# SCH_Joker_2025-09-11.net
KiCad netlist of a schematic drawn in EasyEDA
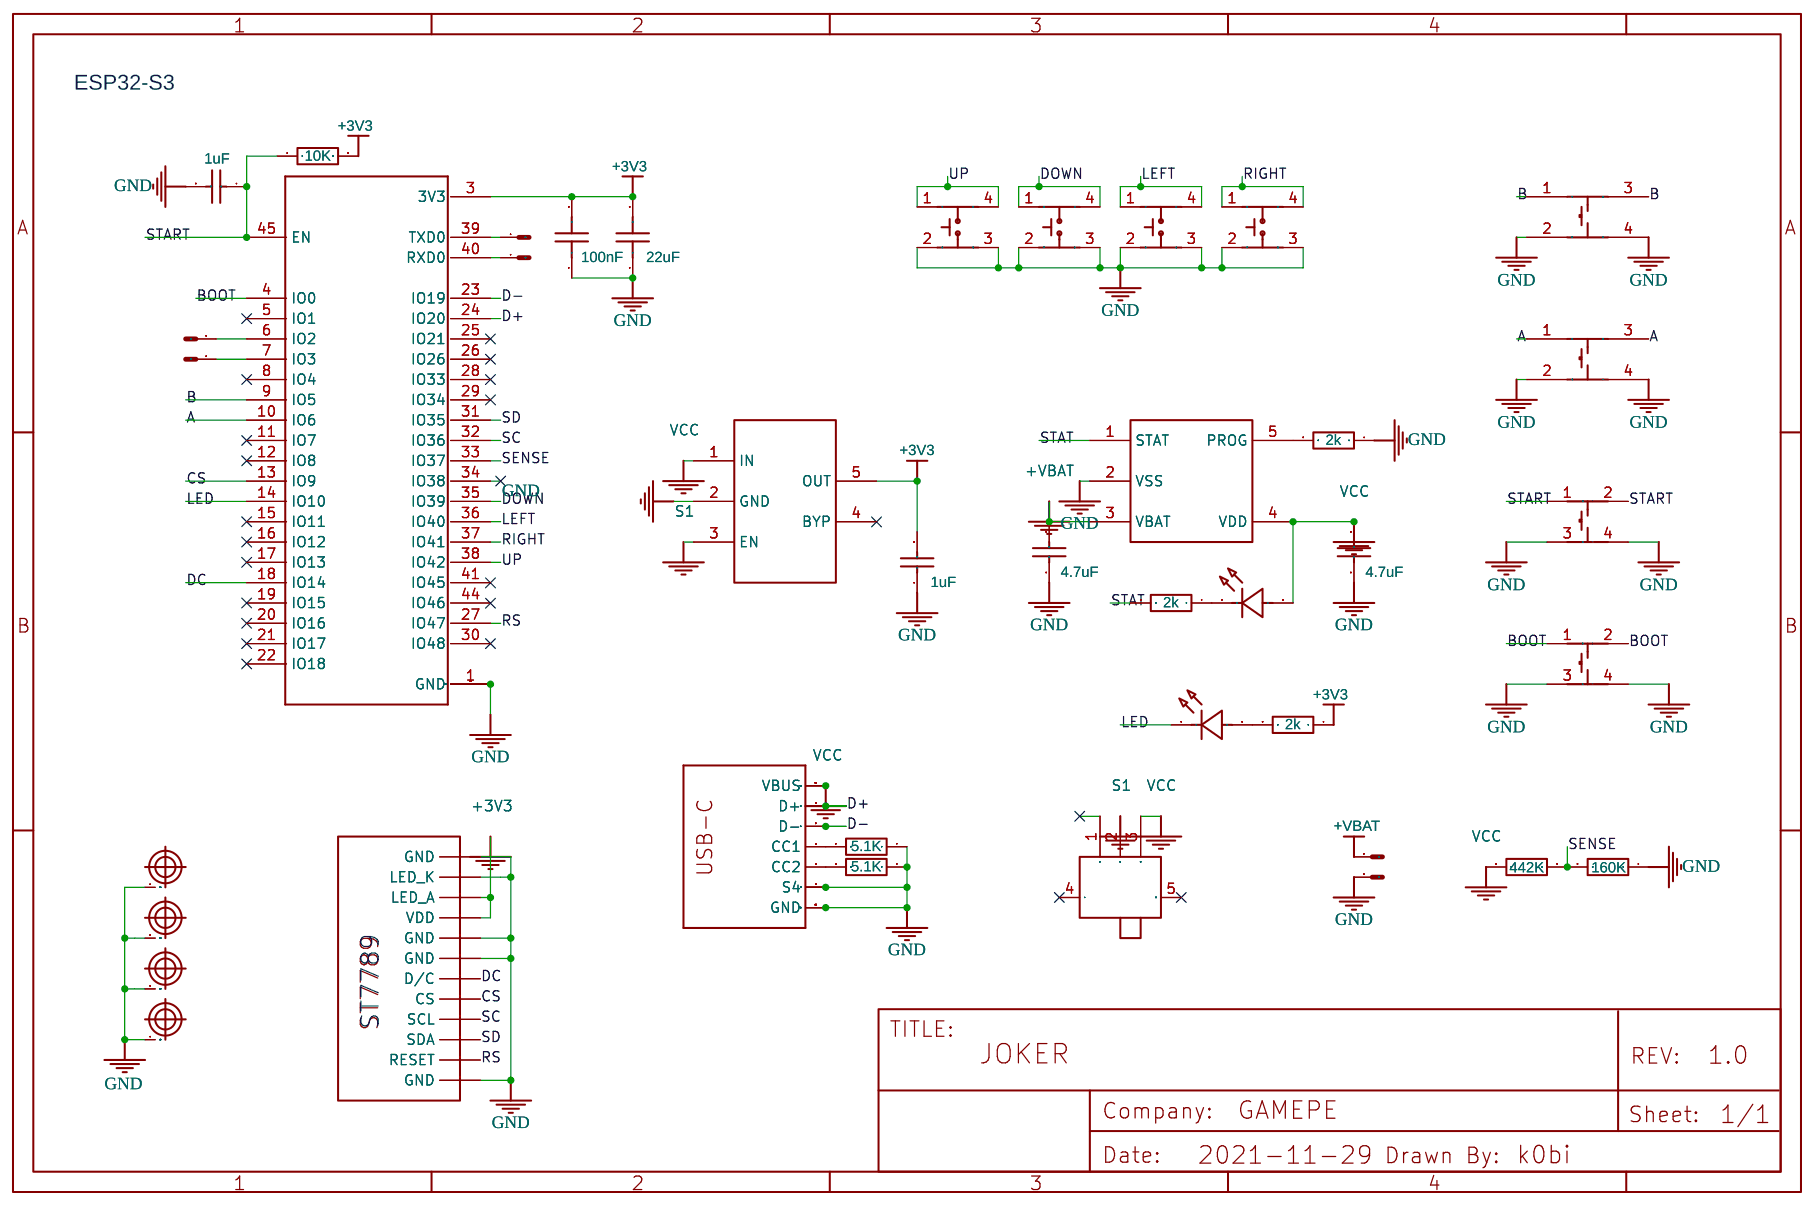
[diagram p0: schematic sheet]

(export (version "E")
  (design (tool "Eeschema 10.0.6"))
  (components
    (comp (ref "C2")
      (value "1uF")
      (fields
        (field (name "Manufacturer Part") "CL10A105KA8NNNC")
        (field (name "Manufacturer") "SAMSUNG(三星)")
      )
      (libsource (lib "") (part "CL10A105KA8NNNC"))
    )
    (comp (ref "C3")
      (value "100nF")
      (fields
        (field (name "Manufacturer Part") "CL10B104KA8NNNC")
        (field (name "Manufacturer") "SAMSUNG(三星)")
      )
      (libsource (lib "") (part "CL10B104KA8NNNC"))
    )
    (comp (ref "C4")
      (value "22uF")
      (fields
        (field (name "Manufacturer Part") "CL10A226MP8NUNE")
        (field (name "Manufacturer") "SAMSUNG(三星)")
      )
      (libsource (lib "") (part "CL10A226MP8NUNE"))
    )
    (comp (ref "C5")
      (value "1uF")
      (fields (field (name "Manufacturer Part") "CC0603MRX5R6BB106") (field (name "Manufacturer") "YAGEO"))
      (libsource (lib "") (part "CC0603MRX5R6BB106"))
    )
    (comp (ref "C6")
      (value "4.7uF")
      (fields (field (name "Manufacturer Part") "CL10A105KA8NNNC") (field (name "Manufacturer") "SAMSUNG"))
      (libsource (lib "") (part "CL10A105KA8NNNC_1"))
    )
    (comp (ref "C7")
      (value "4.7uF")
      (fields (field (name "Manufacturer Part") "CL10A105KA8NNNC") (field (name "Manufacturer") "SAMSUNG"))
      (libsource (lib "") (part "CL10A105KA8NNNC_1"))
    )
    (comp (ref "H1") (value "M2-MOUNT-HOLE") (libsource (lib "") (part "M2-MOUNT-HOLE")))
    (comp (ref "H2") (value "M2-MOUNT-HOLE") (libsource (lib "") (part "M2-MOUNT-HOLE")))
    (comp (ref "H3") (value "M2-MOUNT-HOLE") (libsource (lib "") (part "M2-MOUNT-HOLE")))
    (comp (ref "H4") (value "M2-MOUNT-HOLE") (libsource (lib "") (part "M2-MOUNT-HOLE")))
    (comp (ref "LED1")
      (value "le")
      (fields
        (field (name "Manufacturer Part") "TZ-P2-0603YGTCS1-0.6T")
        (field (name "Manufacturer") "TUOZHAN")
      )
      (libsource (lib "") (part "TZ-P2-0603YGTCS1-0.6T"))
    )
    (comp (ref "LED2")
      (value "le")
      (fields
        (field (name "Manufacturer Part") "TZ-P2-0603YGTCS1-0.6T")
        (field (name "Manufacturer") "TUOZHAN")
      )
      (libsource (lib "") (part "TZ-P2-0603YGTCS1-0.6T"))
    )
    (comp (ref "R1")
      (value "2k")
      (fields (field (name "Manufacturer Part") "RC0603FR-0710KL") (field (name "Manufacturer") "YAGEO"))
      (libsource (lib "") (part "RC0603FR-0710KL"))
    )
    (comp (ref "R2")
      (value "2k")
      (fields (field (name "Manufacturer Part") "RC0603FR-0710KL") (field (name "Manufacturer") "YAGEO"))
      (libsource (lib "") (part "RC0603FR-0710KL"))
    )
    (comp (ref "R6")
      (value "10K")
      (fields (field (name "Manufacturer Part") "RC0603FR-0710KL") (field (name "Manufacturer") "YAGEO(国巨)"))
      (libsource (lib "") (part "RC0603FR-0710KL_1"))
    )
    (comp (ref "R10")
      (value "5.1K")
      (fields (field (name "Manufacturer Part") "RC0603FR-0710KL") (field (name "Manufacturer") "YAGEO"))
      (libsource (lib "") (part "RC0603FR-0710KL"))
    )
    (comp (ref "R11")
      (value "5.1K")
      (fields (field (name "Manufacturer Part") "RC0603FR-0710KL") (field (name "Manufacturer") "YAGEO"))
      (libsource (lib "") (part "RC0603FR-0710KL"))
    )
    (comp (ref "R13")
      (value "2k")
      (fields (field (name "Manufacturer Part") "RC0603FR-0710KL") (field (name "Manufacturer") "YAGEO"))
      (libsource (lib "") (part "RC0603FR-0710KL"))
    )
    (comp (ref "R15")
      (value "442K")
      (fields (field (name "Manufacturer Part") "RC0603FR-0710KL") (field (name "Manufacturer") "YAGEO"))
      (libsource (lib "") (part "RC0603FR-0710KL"))
    )
    (comp (ref "R16")
      (value "160K")
      (fields (field (name "Manufacturer Part") "RC0603FR-0710KL") (field (name "Manufacturer") "YAGEO"))
      (libsource (lib "") (part "RC0603FR-0710KL"))
    )
    (comp (ref "SW1")
      (value "SKRRAAE010")
      (fields (field (name "Manufacturer") "ALPSALPINE(阿尔卑斯阿尔派)"))
      (libsource (lib "") (part "SKRRAAE010"))
    )
    (comp (ref "SW2")
      (value "SKRRAAE010")
      (fields (field (name "Manufacturer") "ALPSALPINE(阿尔卑斯阿尔派)"))
      (libsource (lib "") (part "SKRRAAE010"))
    )
    (comp (ref "SW3")
      (value "TS-2630-B")
      (fields (field (name "Manufacturer") "XKB Connectivity(中国星坤)"))
      (libsource (lib "") (part "TS-2630-B"))
    )
    (comp (ref "SW4")
      (value "TS-2630-B")
      (fields (field (name "Manufacturer") "XKB Connectivity(中国星坤)"))
      (libsource (lib "") (part "TS-2630-B"))
    )
    (comp (ref "SW6")
      (value "C219784")
      (fields
        (field (name "Manufacturer Part") "SKTKABE010")
        (field (name "Manufacturer") "ALPSALPINE(阿尔卑斯阿尔派)")
      )
      (libsource (lib "") (part "C219784"))
    )
    (comp (ref "SW7")
      (value "C219784")
      (fields
        (field (name "Manufacturer Part") "SKTKABE010")
        (field (name "Manufacturer") "ALPSALPINE(阿尔卑斯阿尔派)")
      )
      (libsource (lib "") (part "C219784"))
    )
    (comp (ref "SW8")
      (value "C219784")
      (fields
        (field (name "Manufacturer Part") "SKTKABE010")
        (field (name "Manufacturer") "ALPSALPINE(阿尔卑斯阿尔派)")
      )
      (libsource (lib "") (part "C219784"))
    )
    (comp (ref "SW9")
      (value "C219784")
      (fields
        (field (name "Manufacturer Part") "SKTKABE010")
        (field (name "Manufacturer") "ALPSALPINE(阿尔卑斯阿尔派)")
      )
      (libsource (lib "") (part "C219784"))
    )
    (comp (ref "SW10")
      (value "MINI MSK12CO2")
      (fields (field (name "Manufacturer") "SHOU HAN(首韩)"))
      (libsource (lib "") (part "MINI MSK12CO2"))
    )
    (comp (ref "TP4") (value "TP/SP-1.5X1.0") (libsource (lib "") (part "TP/SP-1.5X1.0")))
    (comp (ref "TP6") (value "TP/SP-1.5X1.0") (libsource (lib "") (part "TP/SP-1.5X1.0")))
    (comp (ref "TP13") (value "TP/SP-1.5X1.0") (libsource (lib "") (part "TP/SP-1.5X1.0_1")))
    (comp (ref "TP14") (value "TP/SP-1.5X1.0") (libsource (lib "") (part "TP/SP-1.5X1.0_1")))
    (comp (ref "TP15") (value "TP/SP-1.5X1.0") (libsource (lib "") (part "TP/SP-1.5X1.0")))
    (comp (ref "TP16") (value "TP/SP-1.5X1.0") (libsource (lib "") (part "TP/SP-1.5X1.0")))
    (comp (ref "U1") (value "ESP32-S3-MINI-1-N8") (libsource (lib "") (part "ESP32-S3-MINI-1-N8")))
    (comp (ref "U2")
      (value "SPX3819M5-L-3-3/TR")
      (fields (field (name "Manufacturer") "EXAR"))
      (libsource (lib "") (part "SPX3819M5-L-3-3/TR"))
    )
    (comp (ref "U3")
      (value "MCP73831T-2ATI/OT")
      (fields (field (name "Manufacturer") "MICROCHIP"))
      (libsource (lib "") (part "MCP73831T-2ATI/OT"))
    )
    (comp (ref "U4")
      (value "1.3\" RGB TFT LCD")
      (fields
        (field (name "Manufacturer Part") "N133-2424TCBIG01-H12")
        (field (name "Manufacturer") "Shenzhen Allvision Tech")
      )
      (libsource (lib "") (part "1.3{dblquote} RGB TFT LCD"))
    )
    (comp (ref "U6") (value "C136423") (libsource (lib "") (part "C136423")))
  )
  (nets
    (net (code "1") (name "+3V3") (class "Default")
      (node (ref "C3") (pin "2") (pinfunction "2_2") (pintype "unspecified"))
      (node (ref "C4") (pin "2") (pinfunction "2_2") (pintype "unspecified"))
      (node (ref "C5") (pin "2") (pinfunction "2_2") (pintype "input"))
      (node (ref "R2") (pin "1") (pinfunction "1_1") (pintype "input"))
      (node (ref "R6") (pin "2") (pinfunction "2_2") (pintype "input"))
      (node (ref "U1") (pin "3") (pinfunction "3V3_3") (pintype "unspecified"))
      (node (ref "U2") (pin "5") (pinfunction "OUT_5") (pintype "unspecified"))
      (node (ref "U4") (pin "3") (pinfunction "LED_A_3") (pintype "unspecified"))
      (node (ref "U4") (pin "4") (pinfunction "VDD_4") (pintype "unspecified"))
    )
    (net (code "2") (name "+VBAT") (class "Default")
      (node (ref "C6") (pin "1") (pinfunction "1_1") (pintype "input"))
      (node (ref "TP16") (pin "1") (pinfunction "S_1") (pintype "bidirectional"))
      (node (ref "U3") (pin "3") (pinfunction "VBAT_3") (pintype "unspecified"))
    )
    (net (code "3") (name "/A") (class "Default")
      (node (ref "SW1") (pin "1") (pinfunction "1_1") (pintype "unspecified"))
      (node (ref "SW1") (pin "3") (pinfunction "3_3") (pintype "unspecified"))
      (node (ref "U1") (pin "10") (pinfunction "IO6_10") (pintype "unspecified"))
    )
    (net (code "4") (name "/B") (class "Default")
      (node (ref "SW2") (pin "1") (pinfunction "1_1") (pintype "unspecified"))
      (node (ref "SW2") (pin "3") (pinfunction "3_3") (pintype "unspecified"))
      (node (ref "U1") (pin "9") (pinfunction "IO5_9") (pintype "unspecified"))
    )
    (net (code "5") (name "/BOOT") (class "Default")
      (node (ref "SW4") (pin "1") (pinfunction "1_1") (pintype "unspecified"))
      (node (ref "SW4") (pin "2") (pinfunction "2_2") (pintype "unspecified"))
      (node (ref "U1") (pin "4") (pinfunction "IO0_4") (pintype "unspecified"))
    )
    (net (code "6") (name "/CS") (class "Default")
      (node (ref "U1") (pin "13") (pinfunction "IO9_13") (pintype "unspecified"))
      (node (ref "U4") (pin "8") (pinfunction "CS_8") (pintype "unspecified"))
    )
    (net (code "7") (name "/D+") (class "Default")
      (node (ref "U1") (pin "24") (pinfunction "IO20_24") (pintype "unspecified"))
      (node (ref "U6") (pin "A6") (pinfunction "D+_A6") (pintype "bidirectional"))
      (node (ref "U6") (pin "B6") (pinfunction "D+_B6") (pintype "bidirectional"))
    )
    (net (code "8") (name "/D-") (class "Default")
      (node (ref "U1") (pin "23") (pinfunction "IO19_23") (pintype "unspecified"))
      (node (ref "U6") (pin "A7") (pinfunction "D-_A7") (pintype "bidirectional"))
      (node (ref "U6") (pin "B7") (pinfunction "D-_B7") (pintype "bidirectional"))
    )
    (net (code "9") (name "/DC") (class "Default")
      (node (ref "U1") (pin "18") (pinfunction "IO14_18") (pintype "unspecified"))
      (node (ref "U4") (pin "7") (pinfunction "D/C_7") (pintype "unspecified"))
    )
    (net (code "10") (name "/DOWN") (class "Default")
      (node (ref "SW8") (pin "1") (pinfunction "1_1") (pintype "unspecified"))
      (node (ref "SW8") (pin "4") (pinfunction "4_4") (pintype "unspecified"))
      (node (ref "U1") (pin "35") (pinfunction "IO39_35") (pintype "unspecified"))
    )
    (net (code "11") (name "/LED") (class "Default")
      (node (ref "LED2") (pin "1") (pinfunction "K_1") (pintype "unspecified"))
      (node (ref "U1") (pin "14") (pinfunction "IO10_14") (pintype "unspecified"))
    )
    (net (code "12") (name "/LEFT") (class "Default")
      (node (ref "SW7") (pin "1") (pinfunction "1_1") (pintype "unspecified"))
      (node (ref "SW7") (pin "4") (pinfunction "4_4") (pintype "unspecified"))
      (node (ref "U1") (pin "36") (pinfunction "IO40_36") (pintype "unspecified"))
    )
    (net (code "13") (name "/RIGHT") (class "Default")
      (node (ref "SW6") (pin "1") (pinfunction "1_1") (pintype "unspecified"))
      (node (ref "SW6") (pin "4") (pinfunction "4_4") (pintype "unspecified"))
      (node (ref "U1") (pin "37") (pinfunction "IO41_37") (pintype "unspecified"))
    )
    (net (code "14") (name "/RS") (class "Default")
      (node (ref "U1") (pin "27") (pinfunction "IO47_27") (pintype "unspecified"))
      (node (ref "U4") (pin "11") (pinfunction "RESET_11") (pintype "unspecified"))
    )
    (net (code "15") (name "/SC") (class "Default")
      (node (ref "U1") (pin "32") (pinfunction "IO36_32") (pintype "unspecified"))
      (node (ref "U4") (pin "9") (pinfunction "SCL_9") (pintype "unspecified"))
    )
    (net (code "16") (name "/SD") (class "Default")
      (node (ref "U1") (pin "31") (pinfunction "IO35_31") (pintype "unspecified"))
      (node (ref "U4") (pin "10") (pinfunction "SDA_10") (pintype "unspecified"))
    )
    (net (code "17") (name "/SENSE") (class "Default")
      (node (ref "R15") (pin "1") (pinfunction "1_1") (pintype "input"))
      (node (ref "R16") (pin "2") (pinfunction "2_2") (pintype "input"))
      (node (ref "U1") (pin "33") (pinfunction "IO37_33") (pintype "unspecified"))
    )
    (net (code "18") (name "/START") (class "Default")
      (node (ref "C2") (pin "1") (pinfunction "1_1") (pintype "input"))
      (node (ref "R6") (pin "1") (pinfunction "1_1") (pintype "input"))
      (node (ref "SW3") (pin "1") (pinfunction "1_1") (pintype "unspecified"))
      (node (ref "SW3") (pin "2") (pinfunction "2_2") (pintype "unspecified"))
      (node (ref "U1") (pin "45") (pinfunction "EN_45") (pintype "unspecified"))
    )
    (net (code "19") (name "/STAT") (class "Default")
      (node (ref "R1") (pin "2") (pinfunction "2_2") (pintype "input"))
      (node (ref "U3") (pin "1") (pinfunction "STAT_1") (pintype "unspecified"))
    )
    (net (code "20") (name "/UP") (class "Default")
      (node (ref "SW9") (pin "1") (pinfunction "1_1") (pintype "unspecified"))
      (node (ref "SW9") (pin "4") (pinfunction "4_4") (pintype "unspecified"))
      (node (ref "U1") (pin "38") (pinfunction "IO42_38") (pintype "unspecified"))
    )
    (net (code "21") (name "GND") (class "Default")
      (node (ref "C2") (pin "2") (pinfunction "2_2") (pintype "input"))
      (node (ref "C3") (pin "1") (pinfunction "1_1") (pintype "unspecified"))
      (node (ref "C4") (pin "1") (pinfunction "1_1") (pintype "unspecified"))
      (node (ref "C5") (pin "1") (pinfunction "1_1") (pintype "input"))
      (node (ref "C6") (pin "2") (pinfunction "2_2") (pintype "input"))
      (node (ref "C7") (pin "2") (pinfunction "2_2") (pintype "input"))
      (node (ref "H1") (pin "1") (pinfunction "GND_1") (pintype "passive"))
      (node (ref "H2") (pin "1") (pinfunction "GND_1") (pintype "passive"))
      (node (ref "H3") (pin "1") (pinfunction "GND_1") (pintype "passive"))
      (node (ref "H4") (pin "1") (pinfunction "GND_1") (pintype "passive"))
      (node (ref "R10") (pin "1") (pinfunction "1_1") (pintype "input"))
      (node (ref "R11") (pin "1") (pinfunction "1_1") (pintype "input"))
      (node (ref "R13") (pin "1") (pinfunction "1_1") (pintype "input"))
      (node (ref "R16") (pin "1") (pinfunction "1_1") (pintype "input"))
      (node (ref "SW1") (pin "2") (pinfunction "2_2") (pintype "unspecified"))
      (node (ref "SW1") (pin "4") (pinfunction "4_4") (pintype "unspecified"))
      (node (ref "SW2") (pin "2") (pinfunction "2_2") (pintype "unspecified"))
      (node (ref "SW2") (pin "4") (pinfunction "4_4") (pintype "unspecified"))
      (node (ref "SW3") (pin "3") (pinfunction "3_3") (pintype "unspecified"))
      (node (ref "SW3") (pin "4") (pinfunction "4_4") (pintype "unspecified"))
      (node (ref "SW4") (pin "3") (pinfunction "3_3") (pintype "unspecified"))
      (node (ref "SW4") (pin "4") (pinfunction "4_4") (pintype "unspecified"))
      (node (ref "SW6") (pin "2") (pinfunction "2_2") (pintype "unspecified"))
      (node (ref "SW6") (pin "3") (pinfunction "3_3") (pintype "unspecified"))
      (node (ref "SW7") (pin "2") (pinfunction "2_2") (pintype "unspecified"))
      (node (ref "SW7") (pin "3") (pinfunction "3_3") (pintype "unspecified"))
      (node (ref "SW8") (pin "2") (pinfunction "2_2") (pintype "unspecified"))
      (node (ref "SW8") (pin "3") (pinfunction "3_3") (pintype "unspecified"))
      (node (ref "SW9") (pin "2") (pinfunction "2_2") (pintype "unspecified"))
      (node (ref "SW9") (pin "3") (pinfunction "3_3") (pintype "unspecified"))
      (node (ref "TP15") (pin "1") (pinfunction "S_1") (pintype "bidirectional"))
      (node (ref "U1") (pin "1") (pinfunction "GND_1") (pintype "unspecified"))
      (node (ref "U1") (pin "2") (pinfunction "GND_2") (pintype "unspecified"))
      (node (ref "U1") (pin "42") (pinfunction "GND_42") (pintype "unspecified"))
      (node (ref "U1") (pin "43") (pinfunction "GND_43") (pintype "unspecified"))
      (node (ref "U1") (pin "46") (pinfunction "GND_46") (pintype "unspecified"))
      (node (ref "U1") (pin "47") (pinfunction "GND_47") (pintype "unspecified"))
      (node (ref "U1") (pin "48") (pinfunction "GND_48") (pintype "unspecified"))
      (node (ref "U1") (pin "49") (pinfunction "GND_49") (pintype "unspecified"))
      (node (ref "U1") (pin "50") (pinfunction "GND_50") (pintype "unspecified"))
      (node (ref "U1") (pin "51") (pinfunction "GND_51") (pintype "unspecified"))
      (node (ref "U1") (pin "52") (pinfunction "GND_52") (pintype "unspecified"))
      (node (ref "U1") (pin "53") (pinfunction "GND_53") (pintype "unspecified"))
      (node (ref "U1") (pin "54") (pinfunction "GND_54") (pintype "unspecified"))
      (node (ref "U1") (pin "55") (pinfunction "GND_55") (pintype "unspecified"))
      (node (ref "U1") (pin "56") (pinfunction "GND_56") (pintype "unspecified"))
      (node (ref "U1") (pin "57") (pinfunction "GND_57") (pintype "unspecified"))
      (node (ref "U1") (pin "58") (pinfunction "GND_58") (pintype "unspecified"))
      (node (ref "U1") (pin "59") (pinfunction "GND_59") (pintype "unspecified"))
      (node (ref "U1") (pin "60") (pinfunction "GND_60") (pintype "unspecified"))
      (node (ref "U1") (pin "61") (pinfunction "GND_61") (pintype "unspecified"))
      (node (ref "U1") (pin "61_1") (pinfunction "GND_61_1") (pintype "unspecified"))
      (node (ref "U1") (pin "61_2") (pinfunction "GND_61_2") (pintype "unspecified"))
      (node (ref "U1") (pin "61_3") (pinfunction "GND_61_3") (pintype "unspecified"))
      (node (ref "U1") (pin "61_4") (pinfunction "GND_61_4") (pintype "unspecified"))
      (node (ref "U1") (pin "61_5") (pinfunction "GND_61_5") (pintype "unspecified"))
      (node (ref "U1") (pin "61_6") (pinfunction "GND_61_6") (pintype "unspecified"))
      (node (ref "U1") (pin "61_7") (pinfunction "GND_61_7") (pintype "unspecified"))
      (node (ref "U1") (pin "61_8") (pinfunction "GND_61_8") (pintype "unspecified"))
      (node (ref "U1") (pin "62") (pinfunction "GND_62") (pintype "unspecified"))
      (node (ref "U1") (pin "63") (pinfunction "GND_63") (pintype "unspecified"))
      (node (ref "U1") (pin "64") (pinfunction "GND_64") (pintype "unspecified"))
      (node (ref "U1") (pin "65") (pinfunction "GND_65") (pintype "unspecified"))
      (node (ref "U2") (pin "2") (pinfunction "GND_2") (pintype "unspecified"))
      (node (ref "U3") (pin "2") (pinfunction "VSS_2") (pintype "unspecified"))
      (node (ref "U4") (pin "1") (pinfunction "GND_1") (pintype "unspecified"))
      (node (ref "U4") (pin "12") (pinfunction "GND_12") (pintype "unspecified"))
      (node (ref "U4") (pin "2") (pinfunction "LED_K_2") (pintype "unspecified"))
      (node (ref "U4") (pin "5") (pinfunction "GND_5") (pintype "unspecified"))
      (node (ref "U4") (pin "6") (pinfunction "GND_6") (pintype "unspecified"))
      (node (ref "U6") (pin "1") (pinfunction "S4_1") (pintype "bidirectional"))
      (node (ref "U6") (pin "2") (pinfunction "S4_2") (pintype "bidirectional"))
      (node (ref "U6") (pin "3") (pinfunction "S4_3") (pintype "bidirectional"))
      (node (ref "U6") (pin "4") (pinfunction "S4_4") (pintype "bidirectional"))
      (node (ref "U6") (pin "A1-B12") (pinfunction "GND_A1-B12") (pintype "bidirectional"))
      (node (ref "U6") (pin "B1-A12") (pinfunction "GND_B1-A12") (pintype "bidirectional"))
    )
    (net (code "22") (name "Net-(LED1-K)") (class "Default")
      (node (ref "LED1") (pin "1") (pinfunction "K_1") (pintype "unspecified"))
      (node (ref "R1") (pin "1") (pinfunction "1_1") (pintype "input"))
    )
    (net (code "23") (name "Net-(LED2-A)") (class "Default")
      (node (ref "LED2") (pin "2") (pinfunction "A_2") (pintype "unspecified"))
      (node (ref "R2") (pin "2") (pinfunction "2_2") (pintype "input"))
    )
    (net (code "24") (name "Net-(TP4-S)") (class "Default")
      (node (ref "TP4") (pin "1") (pinfunction "S_1") (pintype "bidirectional"))
      (node (ref "U1") (pin "39") (pinfunction "TXD0_39") (pintype "unspecified"))
    )
    (net (code "25") (name "Net-(TP6-S)") (class "Default")
      (node (ref "TP6") (pin "1") (pinfunction "S_1") (pintype "bidirectional"))
      (node (ref "U1") (pin "40") (pinfunction "RXD0_40") (pintype "unspecified"))
    )
    (net (code "26") (name "Net-(TP13-S)") (class "Default")
      (node (ref "TP13") (pin "1") (pinfunction "S_1") (pintype "bidirectional"))
      (node (ref "U1") (pin "7") (pinfunction "IO3_7") (pintype "unspecified"))
    )
    (net (code "27") (name "Net-(TP14-S)") (class "Default")
      (node (ref "TP14") (pin "1") (pinfunction "S_1") (pintype "bidirectional"))
      (node (ref "U1") (pin "6") (pinfunction "IO2_6") (pintype "unspecified"))
    )
    (net (code "28") (name "Net-(U3-PROG)") (class "Default")
      (node (ref "R13") (pin "2") (pinfunction "2_2") (pintype "input"))
      (node (ref "U3") (pin "5") (pinfunction "PROG_5") (pintype "unspecified"))
    )
    (net (code "29") (name "Net-(U6-CC1)") (class "Default")
      (node (ref "R10") (pin "2") (pinfunction "2_2") (pintype "input"))
      (node (ref "U6") (pin "A5") (pinfunction "CC1_A5") (pintype "bidirectional"))
    )
    (net (code "30") (name "Net-(U6-CC2)") (class "Default")
      (node (ref "R11") (pin "2") (pinfunction "2_2") (pintype "input"))
      (node (ref "U6") (pin "B5") (pinfunction "CC2_B5") (pintype "bidirectional"))
    )
    (net (code "31") (name "S1") (class "Default")
      (node (ref "SW10") (pin "2") (pinfunction "2_2") (pintype "unspecified"))
      (node (ref "U2") (pin "3") (pinfunction "EN_3") (pintype "unspecified"))
    )
    (net (code "32") (name "VCC") (class "Default")
      (node (ref "C7") (pin "1") (pinfunction "1_1") (pintype "input"))
      (node (ref "LED1") (pin "2") (pinfunction "A_2") (pintype "unspecified"))
      (node (ref "R15") (pin "2") (pinfunction "2_2") (pintype "input"))
      (node (ref "SW10") (pin "3") (pinfunction "3_3") (pintype "unspecified"))
      (node (ref "U2") (pin "1") (pinfunction "IN_1") (pintype "unspecified"))
      (node (ref "U3") (pin "4") (pinfunction "VDD_4") (pintype "unspecified"))
      (node (ref "U6") (pin "A4-B9") (pinfunction "VBUS_A4-B9") (pintype "bidirectional"))
      (node (ref "U6") (pin "B4-A9") (pinfunction "VBUS_B4-A9") (pintype "bidirectional"))
    )
    (net (code "33") (name "unconnected-(SW10-Pad1)") (class "Default")
      (node (ref "SW10") (pin "1") (pinfunction "1_1") (pintype "unspecified+no_connect"))
    )
    (net (code "34") (name "unconnected-(SW10-Pad4)") (class "Default")
      (node (ref "SW10") (pin "4") (pinfunction "4_4") (pintype "unspecified+no_connect"))
    )
    (net (code "35") (name "unconnected-(SW10-Pad5)") (class "Default")
      (node (ref "SW10") (pin "5") (pinfunction "5_5") (pintype "unspecified+no_connect"))
    )
    (net (code "36") (name "unconnected-(U1-IO1-Pad5)") (class "Default")
      (node (ref "U1") (pin "5") (pinfunction "IO1_5") (pintype "unspecified+no_connect"))
    )
    (net (code "37") (name "unconnected-(U1-IO4-Pad8)") (class "Default")
      (node (ref "U1") (pin "8") (pinfunction "IO4_8") (pintype "unspecified+no_connect"))
    )
    (net (code "38") (name "unconnected-(U1-IO7-Pad11)") (class "Default")
      (node (ref "U1") (pin "11") (pinfunction "IO7_11") (pintype "unspecified+no_connect"))
    )
    (net (code "39") (name "unconnected-(U1-IO8-Pad12)") (class "Default")
      (node (ref "U1") (pin "12") (pinfunction "IO8_12") (pintype "unspecified+no_connect"))
    )
    (net (code "40") (name "unconnected-(U1-IO11-Pad15)") (class "Default")
      (node (ref "U1") (pin "15") (pinfunction "IO11_15") (pintype "unspecified+no_connect"))
    )
    (net (code "41") (name "unconnected-(U1-IO12-Pad16)") (class "Default")
      (node (ref "U1") (pin "16") (pinfunction "IO12_16") (pintype "unspecified+no_connect"))
    )
    (net (code "42") (name "unconnected-(U1-IO13-Pad17)") (class "Default")
      (node (ref "U1") (pin "17") (pinfunction "IO13_17") (pintype "unspecified+no_connect"))
    )
    (net (code "43") (name "unconnected-(U1-IO15-Pad19)") (class "Default")
      (node (ref "U1") (pin "19") (pinfunction "IO15_19") (pintype "unspecified+no_connect"))
    )
    (net (code "44") (name "unconnected-(U1-IO16-Pad20)") (class "Default")
      (node (ref "U1") (pin "20") (pinfunction "IO16_20") (pintype "unspecified+no_connect"))
    )
    (net (code "45") (name "unconnected-(U1-IO17-Pad21)") (class "Default")
      (node (ref "U1") (pin "21") (pinfunction "IO17_21") (pintype "unspecified+no_connect"))
    )
    (net (code "46") (name "unconnected-(U1-IO18-Pad22)") (class "Default")
      (node (ref "U1") (pin "22") (pinfunction "IO18_22") (pintype "unspecified+no_connect"))
    )
    (net (code "47") (name "unconnected-(U1-IO21-Pad25)") (class "Default")
      (node (ref "U1") (pin "25") (pinfunction "IO21_25") (pintype "unspecified+no_connect"))
    )
    (net (code "48") (name "unconnected-(U1-IO26-Pad26)") (class "Default")
      (node (ref "U1") (pin "26") (pinfunction "IO26_26") (pintype "unspecified+no_connect"))
    )
    (net (code "49") (name "unconnected-(U1-IO33-Pad28)") (class "Default")
      (node (ref "U1") (pin "28") (pinfunction "IO33_28") (pintype "unspecified+no_connect"))
    )
    (net (code "50") (name "unconnected-(U1-IO34-Pad29)") (class "Default")
      (node (ref "U1") (pin "29") (pinfunction "IO34_29") (pintype "unspecified+no_connect"))
    )
    (net (code "51") (name "unconnected-(U1-IO38-Pad34)") (class "Default")
      (node (ref "U1") (pin "34") (pinfunction "IO38_34") (pintype "unspecified+no_connect"))
    )
    (net (code "52") (name "unconnected-(U1-IO45-Pad41)") (class "Default")
      (node (ref "U1") (pin "41") (pinfunction "IO45_41") (pintype "unspecified"))
    )
    (net (code "53") (name "unconnected-(U1-IO46-Pad44)") (class "Default")
      (node (ref "U1") (pin "44") (pinfunction "IO46_44") (pintype "unspecified"))
    )
    (net (code "54") (name "unconnected-(U1-IO48-Pad30)") (class "Default")
      (node (ref "U1") (pin "30") (pinfunction "IO48_30") (pintype "unspecified+no_connect"))
    )
    (net (code "55") (name "unconnected-(U2-BYP-Pad4)") (class "Default")
      (node (ref "U2") (pin "4") (pinfunction "BYP_4") (pintype "unspecified"))
    )
  )
)
